# Hat_MCP3912.net
KiCad netlist of a schematic drawn in EAGLE
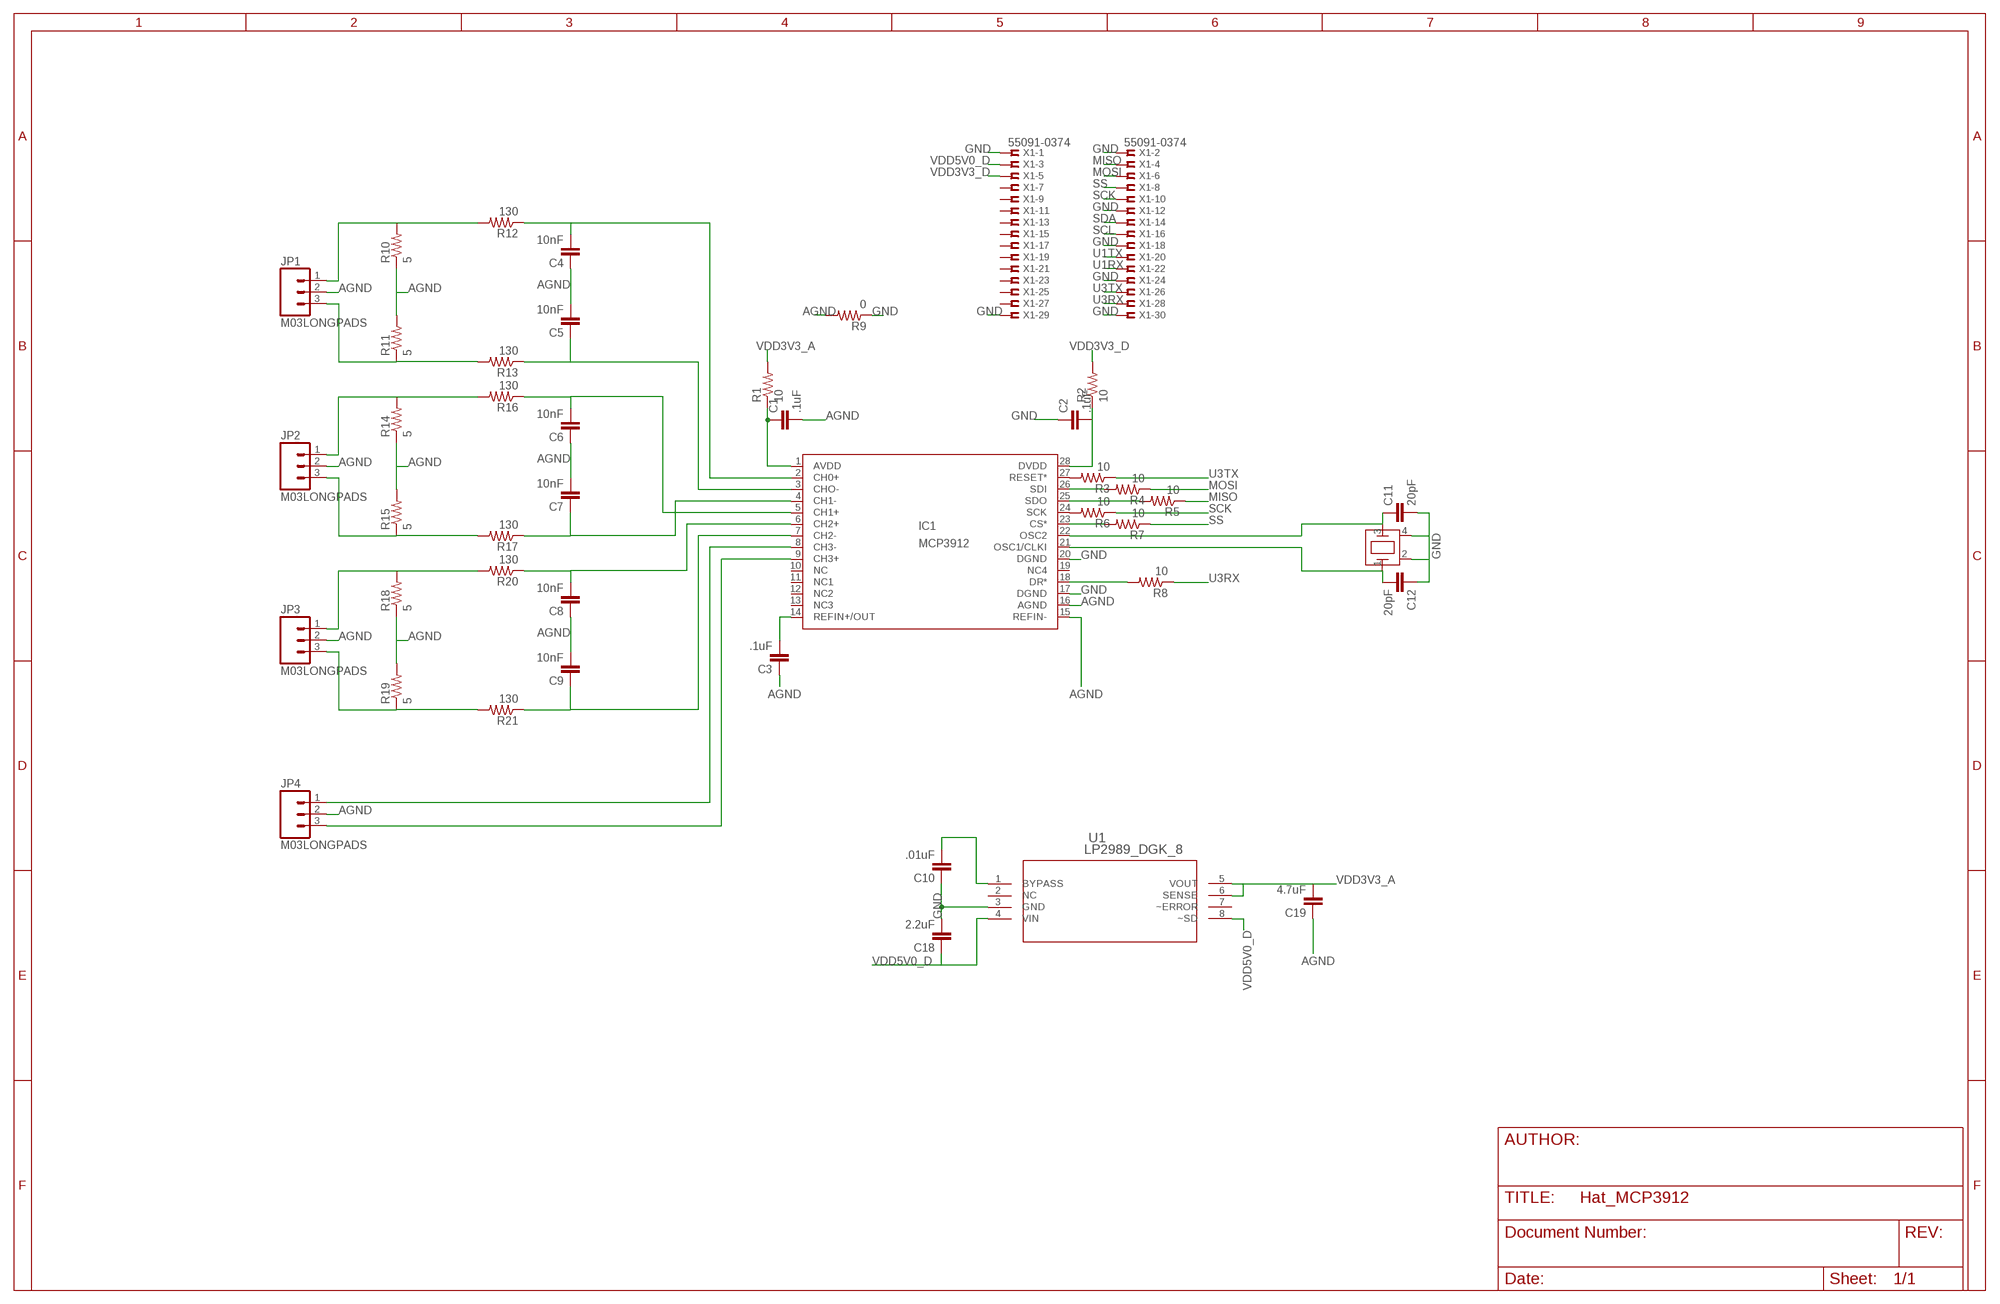
[diagram p0: schematic, sheet 1]

(export (version "E")
  (design (tool "Eeschema 10.0.6"))
  (components
    (comp (ref "C1")
      (value ".1uF")
      (footprint "eagle-import:0805")
      (libsource (lib "eagle-import") (part "CAP0805"))
    )
    (comp (ref "C2")
      (value ".1uF")
      (footprint "eagle-import:0805")
      (libsource (lib "eagle-import") (part "CAP0805"))
    )
    (comp (ref "C3")
      (value ".1uF")
      (footprint "eagle-import:0805")
      (libsource (lib "eagle-import") (part "CAP0805"))
    )
    (comp (ref "C4")
      (value "10nF")
      (footprint "eagle-import:0805")
      (libsource (lib "eagle-import") (part "CAP0805"))
    )
    (comp (ref "C5")
      (value "10nF")
      (footprint "eagle-import:0805")
      (libsource (lib "eagle-import") (part "CAP0805"))
    )
    (comp (ref "C6")
      (value "10nF")
      (footprint "eagle-import:0805")
      (libsource (lib "eagle-import") (part "CAP0805"))
    )
    (comp (ref "C7")
      (value "10nF")
      (footprint "eagle-import:0805")
      (libsource (lib "eagle-import") (part "CAP0805"))
    )
    (comp (ref "C8")
      (value "10nF")
      (footprint "eagle-import:0805")
      (libsource (lib "eagle-import") (part "CAP0805"))
    )
    (comp (ref "C9")
      (value "10nF")
      (footprint "eagle-import:0805")
      (libsource (lib "eagle-import") (part "CAP0805"))
    )
    (comp (ref "C10")
      (value ".01uF")
      (footprint "eagle-import:0805")
      (libsource (lib "eagle-import") (part "CAP0805"))
    )
    (comp (ref "C11")
      (value "20pF")
      (footprint "eagle-import:0805")
      (libsource (lib "eagle-import") (part "CAP0805"))
    )
    (comp (ref "C12")
      (value "20pF")
      (footprint "eagle-import:0805")
      (libsource (lib "eagle-import") (part "CAP0805"))
    )
    (comp (ref "C18")
      (value "2.2uF")
      (footprint "eagle-import:0805")
      (libsource (lib "eagle-import") (part "CAP0805"))
    )
    (comp (ref "C19")
      (value "4.7uF")
      (footprint "eagle-import:0805")
      (libsource (lib "eagle-import") (part "CAP0805"))
    )
    (comp (ref "IC1")
      (value "MCP3912")
      (footprint "eagle-import:SSOP28")
      (libsource (lib "eagle-import") (part "MCP3912"))
    )
    (comp (ref "JP1")
      (value "M03LONGPADS")
      (footprint "eagle-import:1X03_LONGPADS")
      (libsource (lib "eagle-import") (part "M03LONGPADS"))
    )
    (comp (ref "JP2")
      (value "M03LONGPADS")
      (footprint "eagle-import:1X03_LONGPADS")
      (libsource (lib "eagle-import") (part "M03LONGPADS"))
    )
    (comp (ref "JP3")
      (value "M03LONGPADS")
      (footprint "eagle-import:1X03_LONGPADS")
      (libsource (lib "eagle-import") (part "M03LONGPADS"))
    )
    (comp (ref "JP4")
      (value "M03LONGPADS")
      (footprint "eagle-import:1X03_LONGPADS")
      (libsource (lib "eagle-import") (part "M03LONGPADS"))
    )
    (comp (ref "R1")
      (value "10")
      (footprint "eagle-import:0805")
      (libsource (lib "eagle-import") (part "RESISTOR0805-RES"))
    )
    (comp (ref "R2")
      (value "10")
      (footprint "eagle-import:0805")
      (libsource (lib "eagle-import") (part "RESISTOR0805-RES"))
    )
    (comp (ref "R3")
      (value "10")
      (footprint "eagle-import:0805")
      (libsource (lib "eagle-import") (part "RESISTOR0805-RES"))
    )
    (comp (ref "R4")
      (value "10")
      (footprint "eagle-import:0805")
      (libsource (lib "eagle-import") (part "RESISTOR0805-RES"))
    )
    (comp (ref "R5")
      (value "10")
      (footprint "eagle-import:0805")
      (libsource (lib "eagle-import") (part "RESISTOR0805-RES"))
    )
    (comp (ref "R6")
      (value "10")
      (footprint "eagle-import:0805")
      (libsource (lib "eagle-import") (part "RESISTOR0805-RES"))
    )
    (comp (ref "R7")
      (value "10")
      (footprint "eagle-import:0805")
      (libsource (lib "eagle-import") (part "RESISTOR0805-RES"))
    )
    (comp (ref "R8")
      (value "10")
      (footprint "eagle-import:0805")
      (libsource (lib "eagle-import") (part "RESISTOR0805-RES"))
    )
    (comp (ref "R9")
      (value "0")
      (footprint "eagle-import:0805")
      (libsource (lib "eagle-import") (part "RESISTOR0805-RES"))
    )
    (comp (ref "R10")
      (value "5")
      (footprint "eagle-import:0805")
      (libsource (lib "eagle-import") (part "RESISTOR0805-RES"))
    )
    (comp (ref "R11")
      (value "5")
      (footprint "eagle-import:0805")
      (libsource (lib "eagle-import") (part "RESISTOR0805-RES"))
    )
    (comp (ref "R12")
      (value "130")
      (footprint "eagle-import:0805")
      (libsource (lib "eagle-import") (part "RESISTOR0805-RES"))
    )
    (comp (ref "R13")
      (value "130")
      (footprint "eagle-import:0805")
      (libsource (lib "eagle-import") (part "RESISTOR0805-RES"))
    )
    (comp (ref "R14")
      (value "5")
      (footprint "eagle-import:0805")
      (libsource (lib "eagle-import") (part "RESISTOR0805-RES"))
    )
    (comp (ref "R15")
      (value "5")
      (footprint "eagle-import:0805")
      (libsource (lib "eagle-import") (part "RESISTOR0805-RES"))
    )
    (comp (ref "R16")
      (value "130")
      (footprint "eagle-import:0805")
      (libsource (lib "eagle-import") (part "RESISTOR0805-RES"))
    )
    (comp (ref "R17")
      (value "130")
      (footprint "eagle-import:0805")
      (libsource (lib "eagle-import") (part "RESISTOR0805-RES"))
    )
    (comp (ref "R18")
      (value "5")
      (footprint "eagle-import:0805")
      (libsource (lib "eagle-import") (part "RESISTOR0805-RES"))
    )
    (comp (ref "R19")
      (value "5")
      (footprint "eagle-import:0805")
      (libsource (lib "eagle-import") (part "RESISTOR0805-RES"))
    )
    (comp (ref "R20")
      (value "130")
      (footprint "eagle-import:0805")
      (libsource (lib "eagle-import") (part "RESISTOR0805-RES"))
    )
    (comp (ref "R21")
      (value "130")
      (footprint "eagle-import:0805")
      (libsource (lib "eagle-import") (part "RESISTOR0805-RES"))
    )
    (comp (ref "U$1")
      (value "7M-12.000MEEQ-T")
      (footprint "eagle-import:7M-CRYSTAL")
      (libsource (lib "eagle-import") (part "7M-12.000MEEQ-T"))
    )
    (comp (ref "U1")
      (value "LP2989_DGK_8")
      (footprint "eagle-import:MUA08A")
      (fields (field (name "PARTNUMBER") "LP2989AIMM-25"))
      (libsource (lib "eagle-import") (part "LP2989_DGK_8"))
    )
    (comp (ref "X1")
      (value "55091-0374")
      (footprint "eagle-import:55091-0374")
      (libsource (lib "eagle-import") (part "55091-0374"))
    )
  )
  (nets
    (net (code "1") (name "/AGND") (class "Default")
      (node (ref "C1") (pin "2") (pinfunction "2_2") (pintype "passive"))
      (node (ref "C19") (pin "1") (pinfunction "1_1") (pintype "passive"))
      (node (ref "C3") (pin "1") (pinfunction "1_1") (pintype "passive"))
      (node (ref "C4") (pin "1") (pinfunction "1_1") (pintype "passive"))
      (node (ref "C5") (pin "2") (pinfunction "2_2") (pintype "passive"))
      (node (ref "C6") (pin "1") (pinfunction "1_1") (pintype "passive"))
      (node (ref "C7") (pin "2") (pinfunction "2_2") (pintype "passive"))
      (node (ref "C8") (pin "1") (pinfunction "1_1") (pintype "passive"))
      (node (ref "C9") (pin "2") (pinfunction "2_2") (pintype "passive"))
      (node (ref "IC1") (pin "15") (pinfunction "REFIN-_15") (pintype "bidirectional"))
      (node (ref "IC1") (pin "16") (pinfunction "AGND_16") (pintype "bidirectional"))
      (node (ref "JP1") (pin "2") (pinfunction "2_2") (pintype "passive"))
      (node (ref "JP2") (pin "2") (pinfunction "2_2") (pintype "passive"))
      (node (ref "JP3") (pin "2") (pinfunction "2_2") (pintype "passive"))
      (node (ref "JP4") (pin "2") (pinfunction "2_2") (pintype "passive"))
      (node (ref "R10") (pin "1") (pinfunction "1_1") (pintype "passive"))
      (node (ref "R11") (pin "2") (pinfunction "2_2") (pintype "passive"))
      (node (ref "R14") (pin "1") (pinfunction "1_1") (pintype "passive"))
      (node (ref "R15") (pin "2") (pinfunction "2_2") (pintype "passive"))
      (node (ref "R18") (pin "1") (pinfunction "1_1") (pintype "passive"))
      (node (ref "R19") (pin "2") (pinfunction "2_2") (pintype "passive"))
      (node (ref "R9") (pin "2") (pinfunction "2_2") (pintype "passive"))
    )
    (net (code "2") (name "/GND") (class "Default")
      (node (ref "C10") (pin "1") (pinfunction "1_1") (pintype "passive"))
      (node (ref "C11") (pin "2") (pinfunction "2_2") (pintype "passive"))
      (node (ref "C12") (pin "1") (pinfunction "1_1") (pintype "passive"))
      (node (ref "C18") (pin "2") (pinfunction "2_2") (pintype "passive"))
      (node (ref "C2") (pin "1") (pinfunction "1_1") (pintype "passive"))
      (node (ref "IC1") (pin "17") (pinfunction "DGND_17") (pintype "bidirectional"))
      (node (ref "IC1") (pin "20") (pinfunction "DGND_20") (pintype "bidirectional"))
      (node (ref "R9") (pin "1") (pinfunction "1_1") (pintype "passive"))
      (node (ref "U$1") (pin "2") (pinfunction "GND1_2") (pintype "bidirectional"))
      (node (ref "U$1") (pin "4") (pinfunction "GND2_4") (pintype "bidirectional"))
      (node (ref "U1") (pin "3") (pinfunction "GND_3") (pintype "passive"))
      (node (ref "X1") (pin "1") (pinfunction "S_1") (pintype "passive"))
      (node (ref "X1") (pin "12") (pinfunction "S_12") (pintype "passive"))
      (node (ref "X1") (pin "18") (pinfunction "S_18") (pintype "passive"))
      (node (ref "X1") (pin "2") (pinfunction "S_2") (pintype "passive"))
      (node (ref "X1") (pin "24") (pinfunction "S_24") (pintype "passive"))
      (node (ref "X1") (pin "29") (pinfunction "S_29") (pintype "passive"))
      (node (ref "X1") (pin "30") (pinfunction "S_30") (pintype "passive"))
    )
    (net (code "3") (name "/MISO") (class "Default")
      (node (ref "R5") (pin "1") (pinfunction "1_1") (pintype "passive"))
      (node (ref "X1") (pin "4") (pinfunction "S_4") (pintype "passive"))
    )
    (net (code "4") (name "/MOSI") (class "Default")
      (node (ref "R4") (pin "1") (pinfunction "1_1") (pintype "passive"))
      (node (ref "X1") (pin "6") (pinfunction "S_6") (pintype "passive"))
    )
    (net (code "5") (name "/SCK") (class "Default")
      (node (ref "R6") (pin "1") (pinfunction "1_1") (pintype "passive"))
      (node (ref "X1") (pin "10") (pinfunction "S_10") (pintype "passive"))
    )
    (net (code "6") (name "/SCL") (class "Default")
      (node (ref "X1") (pin "16") (pinfunction "S_16") (pintype "passive"))
    )
    (net (code "7") (name "/SDA") (class "Default")
      (node (ref "X1") (pin "14") (pinfunction "S_14") (pintype "passive"))
    )
    (net (code "8") (name "/SS") (class "Default")
      (node (ref "R7") (pin "1") (pinfunction "1_1") (pintype "passive"))
      (node (ref "X1") (pin "8") (pinfunction "S_8") (pintype "passive"))
    )
    (net (code "9") (name "/U1RX") (class "Default")
      (node (ref "X1") (pin "22") (pinfunction "S_22") (pintype "passive"))
    )
    (net (code "10") (name "/U1TX") (class "Default")
      (node (ref "X1") (pin "20") (pinfunction "S_20") (pintype "passive"))
    )
    (net (code "11") (name "/U3RX") (class "Default")
      (node (ref "R8") (pin "1") (pinfunction "1_1") (pintype "passive"))
      (node (ref "X1") (pin "28") (pinfunction "S_28") (pintype "passive"))
    )
    (net (code "12") (name "/U3TX") (class "Default")
      (node (ref "R3") (pin "1") (pinfunction "1_1") (pintype "passive"))
      (node (ref "X1") (pin "26") (pinfunction "S_26") (pintype "passive"))
    )
    (net (code "13") (name "/VDD3V3_A") (class "Default")
      (node (ref "C19") (pin "2") (pinfunction "2_2") (pintype "passive"))
      (node (ref "R1") (pin "2") (pinfunction "2_2") (pintype "passive"))
      (node (ref "U1") (pin "5") (pinfunction "VOUT_5") (pintype "output"))
      (node (ref "U1") (pin "6") (pinfunction "SENSE_6") (pintype "passive"))
    )
    (net (code "14") (name "/VDD3V3_D") (class "Default")
      (node (ref "R2") (pin "2") (pinfunction "2_2") (pintype "passive"))
      (node (ref "X1") (pin "5") (pinfunction "S_5") (pintype "passive"))
    )
    (net (code "15") (name "/VDD5V0_D") (class "Default")
      (node (ref "C18") (pin "1") (pinfunction "1_1") (pintype "passive"))
      (node (ref "U1") (pin "4") (pinfunction "VIN_4") (pintype "input"))
      (node (ref "U1") (pin "8") (pinfunction "~{SD}_8") (pintype "passive"))
      (node (ref "X1") (pin "3") (pinfunction "S_3") (pintype "passive"))
    )
    (net (code "16") (name "Net-(IC1-AVDD)") (class "Default")
      (node (ref "C1") (pin "1") (pinfunction "1_1") (pintype "passive"))
      (node (ref "IC1") (pin "1") (pinfunction "AVDD_1") (pintype "bidirectional"))
      (node (ref "R1") (pin "1") (pinfunction "1_1") (pintype "passive"))
    )
    (net (code "17") (name "Net-(IC1-CH0+)") (class "Default")
      (node (ref "C4") (pin "2") (pinfunction "2_2") (pintype "passive"))
      (node (ref "IC1") (pin "2") (pinfunction "CH0+_2") (pintype "bidirectional"))
      (node (ref "R12") (pin "1") (pinfunction "1_1") (pintype "passive"))
    )
    (net (code "18") (name "Net-(IC1-CH1+)") (class "Default")
      (node (ref "C6") (pin "2") (pinfunction "2_2") (pintype "passive"))
      (node (ref "IC1") (pin "5") (pinfunction "CH1+_5") (pintype "bidirectional"))
      (node (ref "R16") (pin "1") (pinfunction "1_1") (pintype "passive"))
    )
    (net (code "19") (name "Net-(IC1-CH1-)") (class "Default")
      (node (ref "C7") (pin "1") (pinfunction "1_1") (pintype "passive"))
      (node (ref "IC1") (pin "4") (pinfunction "CH1-_4") (pintype "bidirectional"))
      (node (ref "R17") (pin "1") (pinfunction "1_1") (pintype "passive"))
    )
    (net (code "20") (name "Net-(IC1-CH2+)") (class "Default")
      (node (ref "C8") (pin "2") (pinfunction "2_2") (pintype "passive"))
      (node (ref "IC1") (pin "6") (pinfunction "CH2+_6") (pintype "bidirectional"))
      (node (ref "R20") (pin "1") (pinfunction "1_1") (pintype "passive"))
    )
    (net (code "21") (name "Net-(IC1-CH2-)") (class "Default")
      (node (ref "C9") (pin "1") (pinfunction "1_1") (pintype "passive"))
      (node (ref "IC1") (pin "7") (pinfunction "CH2-_7") (pintype "bidirectional"))
      (node (ref "R21") (pin "1") (pinfunction "1_1") (pintype "passive"))
    )
    (net (code "22") (name "Net-(IC1-CH3+)") (class "Default")
      (node (ref "IC1") (pin "9") (pinfunction "CH3+_9") (pintype "bidirectional"))
      (node (ref "JP4") (pin "3") (pinfunction "3_3") (pintype "passive"))
    )
    (net (code "23") (name "Net-(IC1-CH3-)") (class "Default")
      (node (ref "IC1") (pin "8") (pinfunction "CH3-_8") (pintype "bidirectional"))
      (node (ref "JP4") (pin "1") (pinfunction "1_1") (pintype "passive"))
    )
    (net (code "24") (name "Net-(IC1-CHO-)") (class "Default")
      (node (ref "C5") (pin "1") (pinfunction "1_1") (pintype "passive"))
      (node (ref "IC1") (pin "3") (pinfunction "CHO-_3") (pintype "bidirectional"))
      (node (ref "R13") (pin "1") (pinfunction "1_1") (pintype "passive"))
    )
    (net (code "25") (name "Net-(IC1-CS*)") (class "Default")
      (node (ref "IC1") (pin "23") (pinfunction "CS*_23") (pintype "bidirectional"))
      (node (ref "R7") (pin "2") (pinfunction "2_2") (pintype "passive"))
    )
    (net (code "26") (name "Net-(IC1-DR*)") (class "Default")
      (node (ref "IC1") (pin "18") (pinfunction "DR*_18") (pintype "bidirectional"))
      (node (ref "R8") (pin "2") (pinfunction "2_2") (pintype "passive"))
    )
    (net (code "27") (name "Net-(IC1-DVDD)") (class "Default")
      (node (ref "C2") (pin "2") (pinfunction "2_2") (pintype "passive"))
      (node (ref "IC1") (pin "28") (pinfunction "DVDD_28") (pintype "bidirectional"))
      (node (ref "R2") (pin "1") (pinfunction "1_1") (pintype "passive"))
    )
    (net (code "28") (name "Net-(IC1-OSC1{slash}CLKI)") (class "Default")
      (node (ref "C12") (pin "2") (pinfunction "2_2") (pintype "passive"))
      (node (ref "IC1") (pin "21") (pinfunction "OSC1/CLKI_21") (pintype "bidirectional"))
      (node (ref "U$1") (pin "1") (pinfunction "OSC1_1") (pintype "bidirectional"))
    )
    (net (code "29") (name "Net-(IC1-OSC2)") (class "Default")
      (node (ref "C11") (pin "1") (pinfunction "1_1") (pintype "passive"))
      (node (ref "IC1") (pin "22") (pinfunction "OSC2_22") (pintype "bidirectional"))
      (node (ref "U$1") (pin "3") (pinfunction "OSC2_3") (pintype "bidirectional"))
    )
    (net (code "30") (name "Net-(IC1-REFIN+{slash}OUT)") (class "Default")
      (node (ref "C3") (pin "2") (pinfunction "2_2") (pintype "passive"))
      (node (ref "IC1") (pin "14") (pinfunction "REFIN+/OUT_14") (pintype "bidirectional"))
    )
    (net (code "31") (name "Net-(IC1-RESET*)") (class "Default")
      (node (ref "IC1") (pin "27") (pinfunction "RESET*_27") (pintype "bidirectional"))
      (node (ref "R3") (pin "2") (pinfunction "2_2") (pintype "passive"))
    )
    (net (code "32") (name "Net-(IC1-SCK)") (class "Default")
      (node (ref "IC1") (pin "24") (pinfunction "SCK_24") (pintype "bidirectional"))
      (node (ref "R6") (pin "2") (pinfunction "2_2") (pintype "passive"))
    )
    (net (code "33") (name "Net-(IC1-SDI)") (class "Default")
      (node (ref "IC1") (pin "26") (pinfunction "SDI_26") (pintype "bidirectional"))
      (node (ref "R4") (pin "2") (pinfunction "2_2") (pintype "passive"))
    )
    (net (code "34") (name "Net-(IC1-SDO)") (class "Default")
      (node (ref "IC1") (pin "25") (pinfunction "SDO_25") (pintype "bidirectional"))
      (node (ref "R5") (pin "2") (pinfunction "2_2") (pintype "passive"))
    )
    (net (code "35") (name "Net-(JP1-Pad1)") (class "Default")
      (node (ref "JP1") (pin "1") (pinfunction "1_1") (pintype "passive"))
      (node (ref "R10") (pin "2") (pinfunction "2_2") (pintype "passive"))
      (node (ref "R12") (pin "2") (pinfunction "2_2") (pintype "passive"))
    )
    (net (code "36") (name "Net-(JP1-Pad3)") (class "Default")
      (node (ref "JP1") (pin "3") (pinfunction "3_3") (pintype "passive"))
      (node (ref "R11") (pin "1") (pinfunction "1_1") (pintype "passive"))
      (node (ref "R13") (pin "2") (pinfunction "2_2") (pintype "passive"))
    )
    (net (code "37") (name "Net-(JP2-Pad1)") (class "Default")
      (node (ref "JP2") (pin "1") (pinfunction "1_1") (pintype "passive"))
      (node (ref "R14") (pin "2") (pinfunction "2_2") (pintype "passive"))
      (node (ref "R16") (pin "2") (pinfunction "2_2") (pintype "passive"))
    )
    (net (code "38") (name "Net-(JP2-Pad3)") (class "Default")
      (node (ref "JP2") (pin "3") (pinfunction "3_3") (pintype "passive"))
      (node (ref "R15") (pin "1") (pinfunction "1_1") (pintype "passive"))
      (node (ref "R17") (pin "2") (pinfunction "2_2") (pintype "passive"))
    )
    (net (code "39") (name "Net-(JP3-Pad1)") (class "Default")
      (node (ref "JP3") (pin "1") (pinfunction "1_1") (pintype "passive"))
      (node (ref "R18") (pin "2") (pinfunction "2_2") (pintype "passive"))
      (node (ref "R20") (pin "2") (pinfunction "2_2") (pintype "passive"))
    )
    (net (code "40") (name "Net-(JP3-Pad3)") (class "Default")
      (node (ref "JP3") (pin "3") (pinfunction "3_3") (pintype "passive"))
      (node (ref "R19") (pin "1") (pinfunction "1_1") (pintype "passive"))
      (node (ref "R21") (pin "2") (pinfunction "2_2") (pintype "passive"))
    )
    (net (code "41") (name "Net-(U1-BYPASS)") (class "Default")
      (node (ref "C10") (pin "2") (pinfunction "2_2") (pintype "passive"))
      (node (ref "U1") (pin "1") (pinfunction "BYPASS_1") (pintype "passive"))
    )
    (net (code "42") (name "unconnected-(IC1-NC-Pad10)") (class "Default")
      (node (ref "IC1") (pin "10") (pinfunction "NC_10") (pintype "bidirectional"))
    )
    (net (code "43") (name "unconnected-(IC1-NC1-Pad11)") (class "Default")
      (node (ref "IC1") (pin "11") (pinfunction "NC1_11") (pintype "bidirectional"))
    )
    (net (code "44") (name "unconnected-(IC1-NC2-Pad12)") (class "Default")
      (node (ref "IC1") (pin "12") (pinfunction "NC2_12") (pintype "bidirectional"))
    )
    (net (code "45") (name "unconnected-(IC1-NC3-Pad13)") (class "Default")
      (node (ref "IC1") (pin "13") (pinfunction "NC3_13") (pintype "bidirectional"))
    )
    (net (code "46") (name "unconnected-(IC1-NC4-Pad19)") (class "Default")
      (node (ref "IC1") (pin "19") (pinfunction "NC4_19") (pintype "bidirectional"))
    )
    (net (code "47") (name "unconnected-(U1-NC-Pad2)") (class "Default")
      (node (ref "U1") (pin "2") (pinfunction "NC_2") (pintype "passive"))
    )
    (net (code "48") (name "unconnected-(U1-~{ERROR}-Pad7)") (class "Default")
      (node (ref "U1") (pin "7") (pinfunction "~{ERROR}_7") (pintype "passive"))
    )
    (net (code "49") (name "unconnected-(X1AB-S-Pad7)") (class "Default")
      (node (ref "X1") (pin "7") (pinfunction "S_7") (pintype "passive"))
    )
    (net (code "50") (name "unconnected-(X1AD-S-Pad9)") (class "Default")
      (node (ref "X1") (pin "9") (pinfunction "S_9") (pintype "passive"))
    )
    (net (code "51") (name "unconnected-(X1C-S-Pad11)") (class "Default")
      (node (ref "X1") (pin "11") (pinfunction "S_11") (pintype "passive"))
    )
    (net (code "52") (name "unconnected-(X1E-S-Pad13)") (class "Default")
      (node (ref "X1") (pin "13") (pinfunction "S_13") (pintype "passive"))
    )
    (net (code "53") (name "unconnected-(X1G-S-Pad15)") (class "Default")
      (node (ref "X1") (pin "15") (pinfunction "S_15") (pintype "passive"))
    )
    (net (code "54") (name "unconnected-(X1I-S-Pad17)") (class "Default")
      (node (ref "X1") (pin "17") (pinfunction "S_17") (pintype "passive"))
    )
    (net (code "55") (name "unconnected-(X1K-S-Pad19)") (class "Default")
      (node (ref "X1") (pin "19") (pinfunction "S_19") (pintype "passive"))
    )
    (net (code "56") (name "unconnected-(X1N-S-Pad21)") (class "Default")
      (node (ref "X1") (pin "21") (pinfunction "S_21") (pintype "passive"))
    )
    (net (code "57") (name "unconnected-(X1P-S-Pad23)") (class "Default")
      (node (ref "X1") (pin "23") (pinfunction "S_23") (pintype "passive"))
    )
    (net (code "58") (name "unconnected-(X1R-S-Pad25)") (class "Default")
      (node (ref "X1") (pin "25") (pinfunction "S_25") (pintype "passive"))
    )
    (net (code "59") (name "unconnected-(X1T-S-Pad27)") (class "Default")
      (node (ref "X1") (pin "27") (pinfunction "S_27") (pintype "passive"))
    )
  )
)
